# temperature.net
KiCad netlist of a schematic drawn in EAGLE
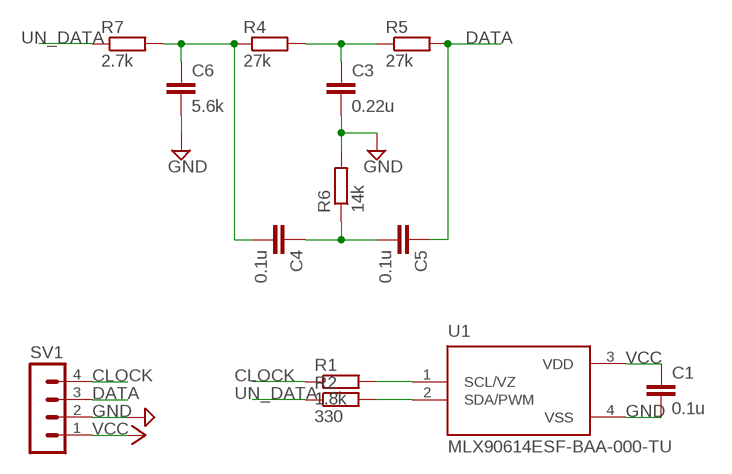
[diagram p0: schematic, sheet 1]

(export (version "E")
  (design (tool "Eeschema 10.0.6"))
  (components
    (comp (ref "C1")
      (value "0.1u")
      (footprint "eagle-import:C0603")
      (libsource (lib "eagle-import") (part "C-EUC0603"))
    )
    (comp (ref "C3")
      (value "0.22u")
      (footprint "eagle-import:C0603")
      (libsource (lib "eagle-import") (part "C-EUC0603"))
    )
    (comp (ref "C4")
      (value "0.1u")
      (footprint "eagle-import:C0603")
      (libsource (lib "eagle-import") (part "C-EUC0603"))
    )
    (comp (ref "C5")
      (value "0.1u")
      (footprint "eagle-import:C0603")
      (libsource (lib "eagle-import") (part "C-EUC0603"))
    )
    (comp (ref "C6")
      (value "5.6k")
      (footprint "eagle-import:C0603")
      (libsource (lib "eagle-import") (part "C-EUC0603"))
    )
    (comp (ref "R1")
      (value "1.8k")
      (footprint "eagle-import:R0603")
      (libsource (lib "eagle-import") (part "R-EU_R0603"))
    )
    (comp (ref "R2")
      (value "330")
      (footprint "eagle-import:R0603")
      (libsource (lib "eagle-import") (part "R-EU_R0603"))
    )
    (comp (ref "R4")
      (value "27k")
      (footprint "eagle-import:R0603")
      (libsource (lib "eagle-import") (part "R-EU_R0603"))
    )
    (comp (ref "R5")
      (value "27k")
      (footprint "eagle-import:R0603")
      (libsource (lib "eagle-import") (part "R-EU_R0603"))
    )
    (comp (ref "R6")
      (value "14k")
      (footprint "eagle-import:R0603")
      (libsource (lib "eagle-import") (part "R-EU_R0603"))
    )
    (comp (ref "R7")
      (value "2.7k")
      (footprint "eagle-import:R0603")
      (libsource (lib "eagle-import") (part "R-EU_R0603"))
    )
    (comp (ref "SV1")
      (value "MA04-1")
      (footprint "eagle-import:MA04-1")
      (libsource (lib "eagle-import") (part "MA04-1"))
    )
    (comp (ref "U1")
      (value "MLX90614ESF-BAA-000-TU")
      (footprint "eagle-import:TO254P942H425-4")
      (fields (field (name "MF") "Melexis"))
      (libsource (lib "eagle-import") (part "MLX90614ESF-BAA-000-TU"))
    )
  )
  (nets
    (net (code "1") (name "/CLOCK") (class "Default")
      (node (ref "R1") (pin "1") (pinfunction "1_1") (pintype "passive"))
      (node (ref "SV1") (pin "4") (pinfunction "4_4") (pintype "passive"))
    )
    (net (code "2") (name "/DATA") (class "Default")
      (node (ref "C5") (pin "1") (pinfunction "1_1") (pintype "passive"))
      (node (ref "R5") (pin "2") (pinfunction "2_2") (pintype "passive"))
      (node (ref "SV1") (pin "3") (pinfunction "3_3") (pintype "passive"))
    )
    (net (code "3") (name "/UN_DATA") (class "Default")
      (node (ref "R2") (pin "1") (pinfunction "1_1") (pintype "passive"))
      (node (ref "R7") (pin "1") (pinfunction "1_1") (pintype "passive"))
    )
    (net (code "4") (name "GND") (class "Default")
      (node (ref "C1") (pin "2") (pinfunction "2_2") (pintype "passive"))
      (node (ref "C3") (pin "2") (pinfunction "2_2") (pintype "passive"))
      (node (ref "C6") (pin "2") (pinfunction "2_2") (pintype "passive"))
      (node (ref "R6") (pin "2") (pinfunction "2_2") (pintype "passive"))
      (node (ref "SV1") (pin "2") (pinfunction "2_2") (pintype "passive"))
      (node (ref "U1") (pin "4") (pinfunction "VSS_4") (pintype "power_in"))
    )
    (net (code "5") (name "Net-(C3-Pad1)") (class "Default")
      (node (ref "C3") (pin "1") (pinfunction "1_1") (pintype "passive"))
      (node (ref "R4") (pin "2") (pinfunction "2_2") (pintype "passive"))
      (node (ref "R5") (pin "1") (pinfunction "1_1") (pintype "passive"))
    )
    (net (code "6") (name "Net-(C4-Pad1)") (class "Default")
      (node (ref "C4") (pin "1") (pinfunction "1_1") (pintype "passive"))
      (node (ref "C5") (pin "2") (pinfunction "2_2") (pintype "passive"))
      (node (ref "R6") (pin "1") (pinfunction "1_1") (pintype "passive"))
    )
    (net (code "7") (name "Net-(C4-Pad2)") (class "Default")
      (node (ref "C4") (pin "2") (pinfunction "2_2") (pintype "passive"))
      (node (ref "C6") (pin "1") (pinfunction "1_1") (pintype "passive"))
      (node (ref "R4") (pin "1") (pinfunction "1_1") (pintype "passive"))
      (node (ref "R7") (pin "2") (pinfunction "2_2") (pintype "passive"))
    )
    (net (code "8") (name "Net-(U1-SCL{slash}VZ)") (class "Default")
      (node (ref "R1") (pin "2") (pinfunction "2_2") (pintype "passive"))
      (node (ref "U1") (pin "1") (pinfunction "SCL/VZ_1") (pintype "input"))
    )
    (net (code "9") (name "Net-(U1-SDA{slash}PWM)") (class "Default")
      (node (ref "R2") (pin "2") (pinfunction "2_2") (pintype "passive"))
      (node (ref "U1") (pin "2") (pinfunction "SDA/PWM_2") (pintype "bidirectional"))
    )
    (net (code "10") (name "VCC") (class "Default")
      (node (ref "C1") (pin "1") (pinfunction "1_1") (pintype "passive"))
      (node (ref "SV1") (pin "1") (pinfunction "1_1") (pintype "passive"))
      (node (ref "U1") (pin "3") (pinfunction "VDD_3") (pintype "power_in"))
    )
  )
)
